# SparkFun_Level_Translator_PCA9306.net
KiCad netlist of a schematic drawn in EAGLE
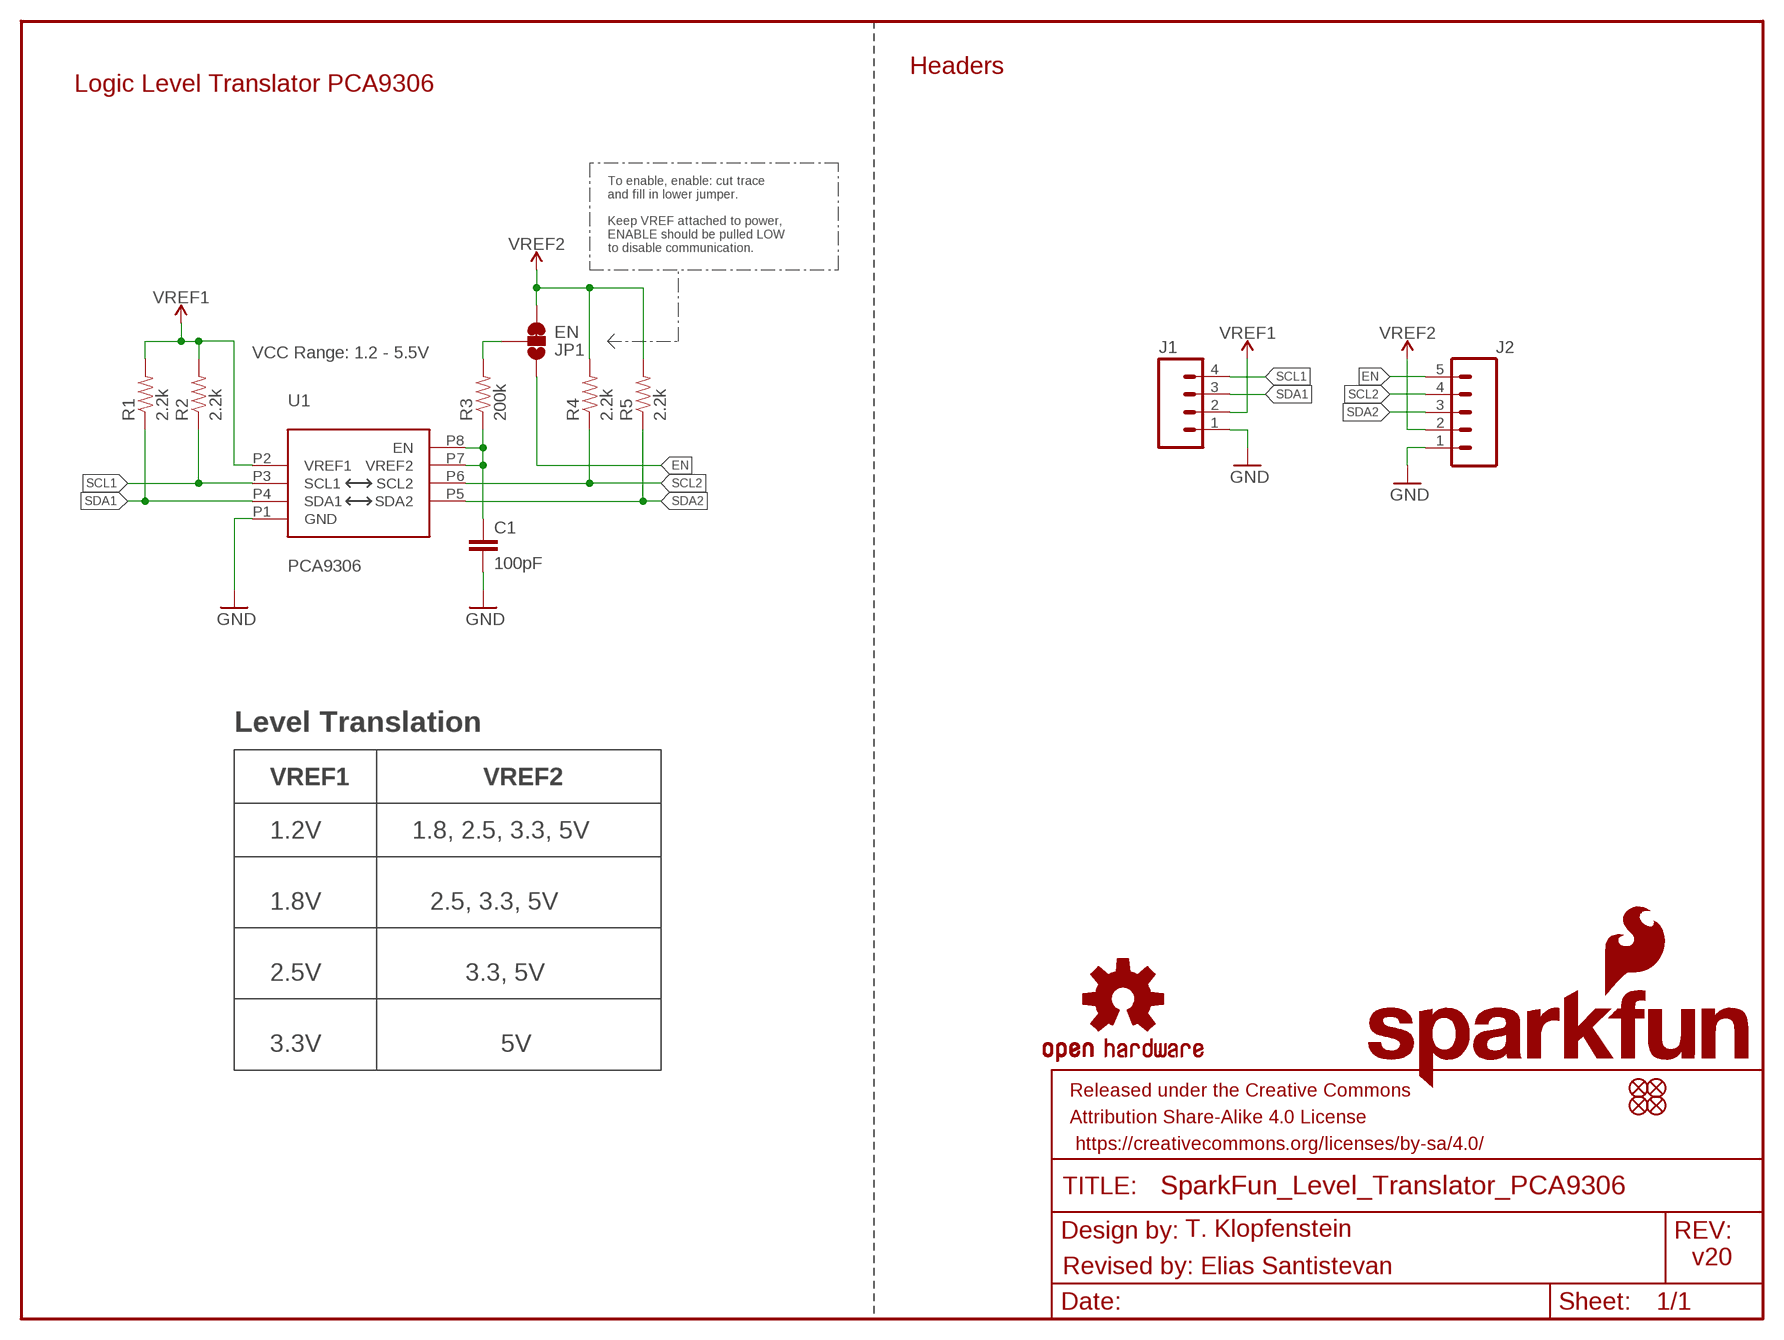
[diagram p0: schematic, sheet 1]

(export (version "E")
  (design (tool "Eeschema 10.0.6"))
  (components
    (comp (ref "C1")
      (value "100pF")
      (footprint "eagle-import:0603")
      (libsource (lib "eagle-import") (part "100PF-0603-50V-5%"))
    )
    (comp (ref "FD1")
      (value "FIDUCIALUFIDUCIAL")
      (footprint "eagle-import:FIDUCIAL-MICRO")
      (libsource (lib "eagle-import") (part "FIDUCIALUFIDUCIAL"))
    )
    (comp (ref "FD2")
      (value "FIDUCIALUFIDUCIAL")
      (footprint "eagle-import:FIDUCIAL-MICRO")
      (libsource (lib "eagle-import") (part "FIDUCIALUFIDUCIAL"))
    )
    (comp (ref "FD3")
      (value "FIDUCIALUFIDUCIAL")
      (footprint "eagle-import:FIDUCIAL-MICRO")
      (libsource (lib "eagle-import") (part "FIDUCIALUFIDUCIAL"))
    )
    (comp (ref "FD4")
      (value "FIDUCIALUFIDUCIAL")
      (footprint "eagle-import:FIDUCIAL-MICRO")
      (libsource (lib "eagle-import") (part "FIDUCIALUFIDUCIAL"))
    )
    (comp (ref "FRAME1")
      (value "FRAME-LETTER")
      (footprint "eagle-import:CREATIVE_COMMONS")
      (libsource (lib "eagle-import") (part "FRAME-LETTER"))
    )
    (comp (ref "J1")
      (value "CONN_041X04_NO_SILK")
      (footprint "eagle-import:1X04_NO_SILK")
      (libsource (lib "eagle-import") (part "CONN_041X04_NO_SILK"))
    )
    (comp (ref "J2")
      (value "CONN_05NO_SILK")
      (footprint "eagle-import:1X05_NO_SILK")
      (libsource (lib "eagle-import") (part "CONN_05NO_SILK"))
    )
    (comp (ref "JP1")
      (value "EN")
      (footprint "eagle-import:SMT-JUMPER_3_1-NC_TRACE_SILK")
      (libsource (lib "eagle-import") (part "JUMPER-SMT_3_1-NC_TRACE_SILK"))
    )
    (comp (ref "LOGO1")
      (value "OSHW-LOGOMINI")
      (footprint "eagle-import:OSHW-LOGO-MINI")
      (libsource (lib "eagle-import") (part "OSHW-LOGOMINI"))
    )
    (comp (ref "LOGO2")
      (value "SFE_LOGO_NAME.1_INCH")
      (footprint "eagle-import:SFE_LOGO_NAME_.1")
      (libsource (lib "eagle-import") (part "SFE_LOGO_NAME.1_INCH"))
    )
    (comp (ref "LOGO3")
      (value "SFE_LOGO_FLAME.1_INCH")
      (footprint "eagle-import:SFE_LOGO_FLAME_.1")
      (libsource (lib "eagle-import") (part "SFE_LOGO_FLAME.1_INCH"))
    )
    (comp (ref "R1")
      (value "2.2k")
      (footprint "eagle-import:0603")
      (libsource (lib "eagle-import") (part "2.2KOHM-0603-1/10W-1%"))
    )
    (comp (ref "R2")
      (value "2.2k")
      (footprint "eagle-import:0603")
      (libsource (lib "eagle-import") (part "2.2KOHM-0603-1/10W-1%"))
    )
    (comp (ref "R3")
      (value "200k")
      (footprint "eagle-import:0603")
      (libsource (lib "eagle-import") (part "200KOHM-0603-1/10W-1%"))
    )
    (comp (ref "R4")
      (value "2.2k")
      (footprint "eagle-import:0603")
      (libsource (lib "eagle-import") (part "2.2KOHM-0603-1/10W-1%"))
    )
    (comp (ref "R5")
      (value "2.2k")
      (footprint "eagle-import:0603")
      (libsource (lib "eagle-import") (part "2.2KOHM-0603-1/10W-1%"))
    )
    (comp (ref "U1")
      (value "PCA9306")
      (footprint "eagle-import:VSSOP_8PIN")
      (libsource (lib "eagle-import") (part "PCA9306VSSOP_8PIN"))
    )
  )
  (nets
    (net (code "1") (name "EN") (class "Default")
      (node (ref "J2") (pin "5") (pinfunction "5_5") (pintype "passive"))
      (node (ref "JP1") (pin "1") (pinfunction "1_1") (pintype "passive"))
    )
    (net (code "2") (name "GND") (class "Default")
      (node (ref "C1") (pin "2") (pinfunction "2_2") (pintype "passive"))
      (node (ref "J1") (pin "1") (pinfunction "1_1") (pintype "passive"))
      (node (ref "J2") (pin "1") (pinfunction "1_1") (pintype "passive"))
      (node (ref "U1") (pin "P1") (pinfunction "GND_P1") (pintype "power_in"))
    )
    (net (code "3") (name "Net-(JP1-Pad2)") (class "Default")
      (node (ref "JP1") (pin "2") (pinfunction "2_2") (pintype "passive"))
      (node (ref "R3") (pin "2") (pinfunction "2_2") (pintype "passive"))
    )
    (net (code "4") (name "Net-(U1-EN)") (class "Default")
      (node (ref "C1") (pin "1") (pinfunction "1_1") (pintype "passive"))
      (node (ref "R3") (pin "1") (pinfunction "1_1") (pintype "passive"))
      (node (ref "U1") (pin "P7") (pinfunction "VREF2_P7") (pintype "power_in"))
      (node (ref "U1") (pin "P8") (pinfunction "EN_P8") (pintype "input"))
    )
    (net (code "5") (name "SCL1") (class "Default")
      (node (ref "J1") (pin "4") (pinfunction "4_4") (pintype "passive"))
      (node (ref "R2") (pin "1") (pinfunction "1_1") (pintype "passive"))
      (node (ref "U1") (pin "P3") (pinfunction "SCL1_P3") (pintype "bidirectional"))
    )
    (net (code "6") (name "SCL2") (class "Default")
      (node (ref "J2") (pin "4") (pinfunction "4_4") (pintype "passive"))
      (node (ref "R4") (pin "1") (pinfunction "1_1") (pintype "passive"))
      (node (ref "U1") (pin "P6") (pinfunction "SCL2_P6") (pintype "bidirectional"))
    )
    (net (code "7") (name "SDA1") (class "Default")
      (node (ref "J1") (pin "3") (pinfunction "3_3") (pintype "passive"))
      (node (ref "R1") (pin "1") (pinfunction "1_1") (pintype "passive"))
      (node (ref "U1") (pin "P4") (pinfunction "SDA1_P4") (pintype "bidirectional"))
    )
    (net (code "8") (name "SDA2") (class "Default")
      (node (ref "J2") (pin "3") (pinfunction "3_3") (pintype "passive"))
      (node (ref "R5") (pin "1") (pinfunction "1_1") (pintype "passive"))
      (node (ref "U1") (pin "P5") (pinfunction "SDA2_P5") (pintype "bidirectional"))
    )
    (net (code "9") (name "VREF1") (class "Default")
      (node (ref "J1") (pin "2") (pinfunction "2_2") (pintype "passive"))
      (node (ref "R1") (pin "2") (pinfunction "2_2") (pintype "passive"))
      (node (ref "R2") (pin "2") (pinfunction "2_2") (pintype "passive"))
      (node (ref "U1") (pin "P2") (pinfunction "VREF1_P2") (pintype "power_in"))
    )
    (net (code "10") (name "VREF2") (class "Default")
      (node (ref "J2") (pin "2") (pinfunction "2_2") (pintype "passive"))
      (node (ref "JP1") (pin "3") (pinfunction "3_3") (pintype "passive"))
      (node (ref "R4") (pin "2") (pinfunction "2_2") (pintype "passive"))
      (node (ref "R5") (pin "2") (pinfunction "2_2") (pintype "passive"))
    )
  )
)
